# Web_Radio_Control_morse_key_USB_adapter.net
KiCad netlist of a schematic drawn in EasyEDA
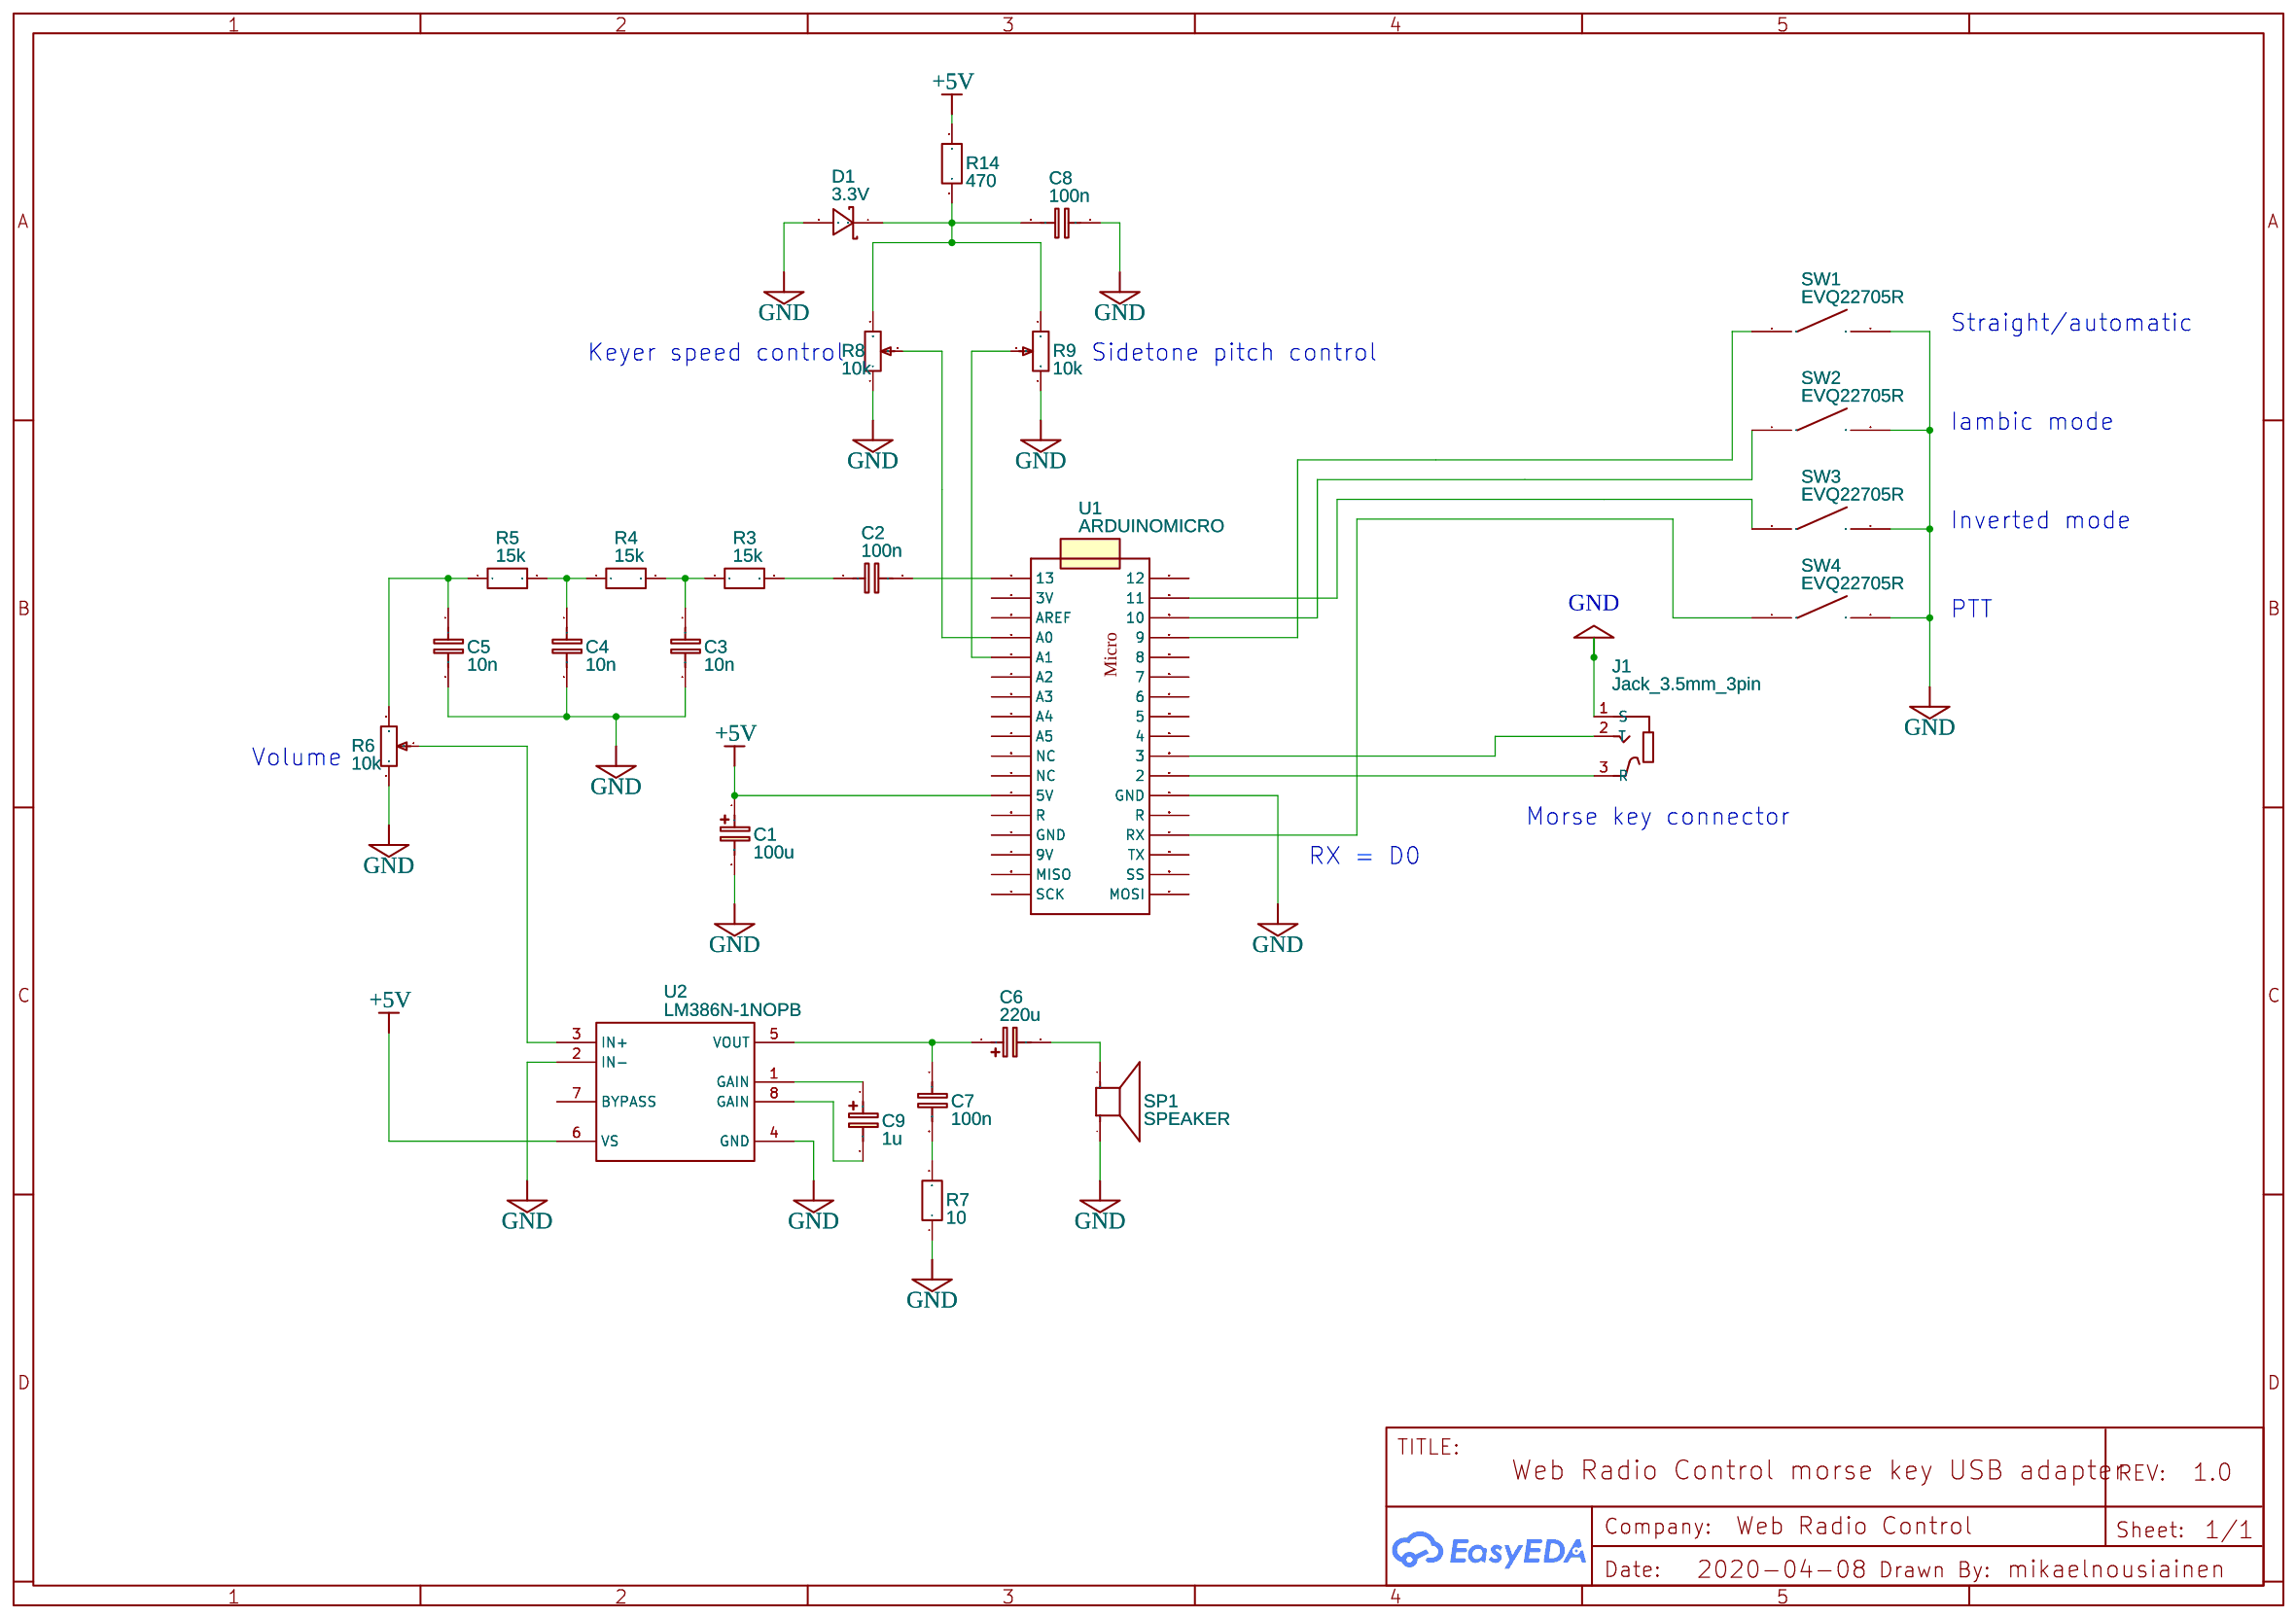
[diagram p0: schematic sheet]

(export (version "E")
  (design (tool "Eeschema 10.0.6"))
  (components
    (comp (ref "C1") (value "100u") (libsource (lib "") (part "Cap_Electrolytic(TH)_D3.0XF1.5_EU")))
    (comp (ref "C2") (value "100n") (libsource (lib "") (part "Cap_RAD-0.1_EU")))
    (comp (ref "C3") (value "10n") (libsource (lib "") (part "Cap_RAD-0.1_EU_2")))
    (comp (ref "C4") (value "10n") (libsource (lib "") (part "Cap_RAD-0.1_EU_2")))
    (comp (ref "C5") (value "10n") (libsource (lib "") (part "Cap_RAD-0.1_EU_2")))
    (comp (ref "C6") (value "220u") (libsource (lib "") (part "Cap_Electrolytic(TH)_D3.0XF1.5_EU_1")))
    (comp (ref "C7") (value "100n") (libsource (lib "") (part "Cap_RAD-0.1_EU_2")))
    (comp (ref "C8") (value "100n") (libsource (lib "") (part "Cap_RAD-0.1_EU_1")))
    (comp (ref "C9") (value "1u") (libsource (lib "") (part "Cap_Electrolytic(TH)_D3.0XF1.5_EU_2")))
    (comp (ref "D1")
      (value "3.3V")
      (fields
        (field (name "BOM_Manufacturer Part") "MBR0520LT1G")
        (field (name "BOM_Supplier Part") "C23848")
      )
      (libsource (lib "") (part "MBR0520LT1G"))
    )
    (comp (ref "J1") (value "Jack_3.5mm_3pin") (libsource (lib "") (part "Jack_3.5mm_3pin")))
    (comp (ref "R3") (value "15k") (libsource (lib "") (part "Res_AXIAL-0.3(1/8W)_EU_2")))
    (comp (ref "R4") (value "15k") (libsource (lib "") (part "Res_AXIAL-0.3(1/8W)_EU_2")))
    (comp (ref "R5") (value "15k") (libsource (lib "") (part "Res_AXIAL-0.3(1/8W)_EU_2")))
    (comp (ref "R6")
      (value "10k")
      (fields
        (field (name "BOM_Manufacturer Part") "3386P-1-101LF")
        (field (name "BOM_Supplier Part") "C125022")
      )
      (libsource (lib "") (part "3386P-1-101LF"))
    )
    (comp (ref "R7") (value "10") (libsource (lib "") (part "Res_AXIAL-0.3(1/8W)_EU")))
    (comp (ref "R8")
      (value "10k")
      (fields
        (field (name "BOM_Manufacturer Part") "3386P-1-101LF")
        (field (name "BOM_Supplier Part") "C125022")
      )
      (libsource (lib "") (part "3386P-1-101LF"))
    )
    (comp (ref "R9")
      (value "10k")
      (fields
        (field (name "BOM_Manufacturer Part") "3386P-1-101LF")
        (field (name "BOM_Supplier Part") "C125022")
      )
      (libsource (lib "") (part "3386P-1-101LF_1"))
    )
    (comp (ref "R14") (value "470") (libsource (lib "") (part "Res_AXIAL-0.3(1/8W)_EU_1")))
    (comp (ref "SP1") (value "SPEAKER") (libsource (lib "") (part "SPEAKER")))
    (comp (ref "SW1")
      (value "EVQ22705R")
      (fields (field (name "BOM_Supplier Part") "C79156"))
      (libsource (lib "") (part "EVQ22705R"))
    )
    (comp (ref "SW2")
      (value "EVQ22705R")
      (fields (field (name "BOM_Supplier Part") "C79156"))
      (libsource (lib "") (part "EVQ22705R"))
    )
    (comp (ref "SW3")
      (value "EVQ22705R")
      (fields (field (name "BOM_Supplier Part") "C79156"))
      (libsource (lib "") (part "EVQ22705R"))
    )
    (comp (ref "SW4")
      (value "EVQ22705R")
      (fields (field (name "BOM_Supplier Part") "C79156"))
      (libsource (lib "") (part "EVQ22705R"))
    )
    (comp (ref "U1") (value "ARDUINOMICRO") (libsource (lib "") (part "ARDUINOMICRO")))
    (comp (ref "U2") (value "LM386N-1NOPB") (libsource (lib "") (part "LM386N-1NOPB")))
  )
  (nets
    (net (code "1") (name "+5V") (class "Default")
      (node (ref "C1") (pin "1") (pinfunction "1_1") (pintype "unspecified"))
      (node (ref "R14") (pin "1") (pinfunction "1_1") (pintype "unspecified"))
      (node (ref "U1") (pin "P$23") (pinfunction "5V_P$23") (pintype "unspecified"))
      (node (ref "U2") (pin "6") (pinfunction "VS_6") (pintype "passive"))
    )
    (net (code "2") (name "GND") (class "Default")
      (node (ref "C1") (pin "2") (pinfunction "2_2") (pintype "unspecified"))
      (node (ref "C3") (pin "2") (pinfunction "2_2") (pintype "unspecified"))
      (node (ref "C4") (pin "2") (pinfunction "2_2") (pintype "unspecified"))
      (node (ref "C5") (pin "2") (pinfunction "2_2") (pintype "unspecified"))
      (node (ref "C8") (pin "1") (pinfunction "1_1") (pintype "unspecified"))
      (node (ref "D1") (pin "2") (pinfunction "A_2") (pintype "unspecified"))
      (node (ref "J1") (pin "1") (pinfunction "S_1") (pintype "unspecified"))
      (node (ref "R6") (pin "1") (pinfunction "1_1") (pintype "input"))
      (node (ref "R7") (pin "1") (pinfunction "1_1") (pintype "unspecified"))
      (node (ref "R8") (pin "1") (pinfunction "1_1") (pintype "input"))
      (node (ref "R9") (pin "3") (pinfunction "3_3") (pintype "input"))
      (node (ref "SP1") (pin "-") (pinfunction "-_-") (pintype "unspecified"))
      (node (ref "SW1") (pin "2") (pinfunction "2_2") (pintype "input"))
      (node (ref "SW2") (pin "2") (pinfunction "2_2") (pintype "input"))
      (node (ref "SW3") (pin "2") (pinfunction "2_2") (pintype "input"))
      (node (ref "SW4") (pin "2") (pinfunction "2_2") (pintype "input"))
      (node (ref "U1") (pin "P$21") (pinfunction "GND_P$21") (pintype "unspecified"))
      (node (ref "U2") (pin "2") (pinfunction "IN-_2") (pintype "unspecified"))
      (node (ref "U2") (pin "4") (pinfunction "GND_4") (pintype "passive"))
    )
    (net (code "3") (name "Net-(C2-Pad1)") (class "Default")
      (node (ref "C2") (pin "1") (pinfunction "1_1") (pintype "unspecified"))
      (node (ref "R3") (pin "2") (pinfunction "2_2") (pintype "unspecified"))
    )
    (net (code "4") (name "Net-(C3-Pad1)") (class "Default")
      (node (ref "C3") (pin "1") (pinfunction "1_1") (pintype "unspecified"))
      (node (ref "R3") (pin "1") (pinfunction "1_1") (pintype "unspecified"))
      (node (ref "R4") (pin "2") (pinfunction "2_2") (pintype "unspecified"))
    )
    (net (code "5") (name "Net-(C4-Pad1)") (class "Default")
      (node (ref "C4") (pin "1") (pinfunction "1_1") (pintype "unspecified"))
      (node (ref "R4") (pin "1") (pinfunction "1_1") (pintype "unspecified"))
      (node (ref "R5") (pin "2") (pinfunction "2_2") (pintype "unspecified"))
    )
    (net (code "6") (name "Net-(C5-Pad1)") (class "Default")
      (node (ref "C5") (pin "1") (pinfunction "1_1") (pintype "unspecified"))
      (node (ref "R5") (pin "1") (pinfunction "1_1") (pintype "unspecified"))
      (node (ref "R6") (pin "3") (pinfunction "3_3") (pintype "input"))
    )
    (net (code "7") (name "Net-(C6-Pad2)") (class "Default")
      (node (ref "C6") (pin "2") (pinfunction "2_2") (pintype "unspecified"))
      (node (ref "SP1") (pin "+") (pinfunction "+_+") (pintype "unspecified"))
    )
    (net (code "8") (name "Net-(C7-Pad2)") (class "Default")
      (node (ref "C7") (pin "2") (pinfunction "2_2") (pintype "unspecified"))
      (node (ref "R7") (pin "2") (pinfunction "2_2") (pintype "unspecified"))
    )
    (net (code "9") (name "Net-(C9-Pad1)") (class "Default")
      (node (ref "C9") (pin "1") (pinfunction "1_1") (pintype "unspecified"))
      (node (ref "U2") (pin "1") (pinfunction "GAIN_1") (pintype "unspecified"))
    )
    (net (code "10") (name "Net-(C9-Pad2)") (class "Default")
      (node (ref "C9") (pin "2") (pinfunction "2_2") (pintype "unspecified"))
      (node (ref "U2") (pin "8") (pinfunction "GAIN_8") (pintype "unspecified"))
    )
    (net (code "11") (name "Net-(D1-C)") (class "Default")
      (node (ref "C8") (pin "2") (pinfunction "2_2") (pintype "unspecified"))
      (node (ref "D1") (pin "1") (pinfunction "C_1") (pintype "unspecified"))
      (node (ref "R14") (pin "2") (pinfunction "2_2") (pintype "unspecified"))
      (node (ref "R8") (pin "3") (pinfunction "3_3") (pintype "input"))
      (node (ref "R9") (pin "1") (pinfunction "1_1") (pintype "input"))
    )
    (net (code "12") (name "Net-(J1-R)") (class "Default")
      (node (ref "J1") (pin "3") (pinfunction "R_3") (pintype "unspecified"))
      (node (ref "U1") (pin "P$11") (pinfunction "2_P$11") (pintype "unspecified"))
    )
    (net (code "13") (name "Net-(J1-T)") (class "Default")
      (node (ref "J1") (pin "2") (pinfunction "T_2") (pintype "unspecified"))
      (node (ref "U1") (pin "P$10") (pinfunction "3_P$10") (pintype "unspecified"))
    )
    (net (code "14") (name "Net-(U1-9)") (class "Default")
      (node (ref "SW1") (pin "1") (pinfunction "1_1") (pintype "input"))
      (node (ref "U1") (pin "P$4") (pinfunction "9_P$4") (pintype "unspecified"))
    )
    (net (code "15") (name "Net-(U1-10)") (class "Default")
      (node (ref "SW2") (pin "1") (pinfunction "1_1") (pintype "input"))
      (node (ref "U1") (pin "P$3") (pinfunction "10_P$3") (pintype "unspecified"))
    )
    (net (code "16") (name "Net-(U1-11)") (class "Default")
      (node (ref "SW3") (pin "1") (pinfunction "1_1") (pintype "input"))
      (node (ref "U1") (pin "P$2") (pinfunction "11_P$2") (pintype "unspecified"))
    )
    (net (code "17") (name "Net-(U1-13)") (class "Default")
      (node (ref "C2") (pin "2") (pinfunction "2_2") (pintype "unspecified"))
      (node (ref "U1") (pin "P$34") (pinfunction "13_P$34") (pintype "unspecified"))
    )
    (net (code "18") (name "Net-(U1-A0)") (class "Default")
      (node (ref "R8") (pin "2") (pinfunction "2_2") (pintype "input"))
      (node (ref "U1") (pin "P$31") (pinfunction "A0_P$31") (pintype "unspecified"))
    )
    (net (code "19") (name "Net-(U1-A1)") (class "Default")
      (node (ref "R9") (pin "2") (pinfunction "2_2") (pintype "input"))
      (node (ref "U1") (pin "P$30") (pinfunction "A1_P$30") (pintype "unspecified"))
    )
    (net (code "20") (name "Net-(U1-RX)") (class "Default")
      (node (ref "SW4") (pin "1") (pinfunction "1_1") (pintype "input"))
      (node (ref "U1") (pin "P$14") (pinfunction "RX_P$14") (pintype "unspecified"))
    )
    (net (code "21") (name "Net-(U2-IN+)") (class "Default")
      (node (ref "R6") (pin "2") (pinfunction "2_2") (pintype "input"))
      (node (ref "U2") (pin "3") (pinfunction "IN+_3") (pintype "unspecified"))
    )
    (net (code "22") (name "Net-(U2-VOUT)") (class "Default")
      (node (ref "C6") (pin "1") (pinfunction "1_1") (pintype "unspecified"))
      (node (ref "C7") (pin "1") (pinfunction "1_1") (pintype "unspecified"))
      (node (ref "U2") (pin "5") (pinfunction "VOUT_5") (pintype "output"))
    )
    (net (code "23") (name "unconnected-(U1-3V-PadP$33)") (class "Default")
      (node (ref "U1") (pin "P$33") (pinfunction "3V_P$33") (pintype "unspecified"))
    )
    (net (code "24") (name "unconnected-(U1-4-PadP$9)") (class "Default")
      (node (ref "U1") (pin "P$9") (pinfunction "4_P$9") (pintype "unspecified"))
    )
    (net (code "25") (name "unconnected-(U1-5-PadP$8)") (class "Default")
      (node (ref "U1") (pin "P$8") (pinfunction "5_P$8") (pintype "unspecified"))
    )
    (net (code "26") (name "unconnected-(U1-6-PadP$7)") (class "Default")
      (node (ref "U1") (pin "P$7") (pinfunction "6_P$7") (pintype "unspecified"))
    )
    (net (code "27") (name "unconnected-(U1-7-PadP$6)") (class "Default")
      (node (ref "U1") (pin "P$6") (pinfunction "7_P$6") (pintype "unspecified"))
    )
    (net (code "28") (name "unconnected-(U1-8-PadP$5)") (class "Default")
      (node (ref "U1") (pin "P$5") (pinfunction "8_P$5") (pintype "unspecified"))
    )
    (net (code "29") (name "unconnected-(U1-9V-PadP$20)") (class "Default")
      (node (ref "U1") (pin "P$20") (pinfunction "9V_P$20") (pintype "unspecified"))
    )
    (net (code "30") (name "unconnected-(U1-12-PadP$1)") (class "Default")
      (node (ref "U1") (pin "P$1") (pinfunction "12_P$1") (pintype "unspecified"))
    )
    (net (code "31") (name "unconnected-(U1-A2-PadP$29)") (class "Default")
      (node (ref "U1") (pin "P$29") (pinfunction "A2_P$29") (pintype "unspecified"))
    )
    (net (code "32") (name "unconnected-(U1-A3-PadP$28)") (class "Default")
      (node (ref "U1") (pin "P$28") (pinfunction "A3_P$28") (pintype "unspecified"))
    )
    (net (code "33") (name "unconnected-(U1-A4-PadP$27)") (class "Default")
      (node (ref "U1") (pin "P$27") (pinfunction "A4_P$27") (pintype "unspecified"))
    )
    (net (code "34") (name "unconnected-(U1-A5-PadP$26)") (class "Default")
      (node (ref "U1") (pin "P$26") (pinfunction "A5_P$26") (pintype "unspecified"))
    )
    (net (code "35") (name "unconnected-(U1-AREF-PadP$32)") (class "Default")
      (node (ref "U1") (pin "P$32") (pinfunction "AREF_P$32") (pintype "unspecified"))
    )
    (net (code "36") (name "unconnected-(U1-GND-PadP$12)") (class "Default")
      (node (ref "U1") (pin "P$12") (pinfunction "GND_P$12") (pintype "unspecified"))
    )
    (net (code "37") (name "unconnected-(U1-MISO-PadP$19)") (class "Default")
      (node (ref "U1") (pin "P$19") (pinfunction "MISO_P$19") (pintype "unspecified"))
    )
    (net (code "38") (name "unconnected-(U1-MOSI-PadP$17)") (class "Default")
      (node (ref "U1") (pin "P$17") (pinfunction "MOSI_P$17") (pintype "unspecified"))
    )
    (net (code "39") (name "unconnected-(U1-NC-PadP$24)") (class "Default")
      (node (ref "U1") (pin "P$24") (pinfunction "NC_P$24") (pintype "unspecified"))
    )
    (net (code "40") (name "unconnected-(U1-NC-PadP$25)") (class "Default")
      (node (ref "U1") (pin "P$25") (pinfunction "NC_P$25") (pintype "unspecified"))
    )
    (net (code "41") (name "unconnected-(U1-R-PadP$13)") (class "Default")
      (node (ref "U1") (pin "P$13") (pinfunction "R_P$13") (pintype "unspecified"))
    )
    (net (code "42") (name "unconnected-(U1-R-PadP$22)") (class "Default")
      (node (ref "U1") (pin "P$22") (pinfunction "R_P$22") (pintype "unspecified"))
    )
    (net (code "43") (name "unconnected-(U1-SCK-PadP$18)") (class "Default")
      (node (ref "U1") (pin "P$18") (pinfunction "SCK_P$18") (pintype "unspecified"))
    )
    (net (code "44") (name "unconnected-(U1-SS-PadP$16)") (class "Default")
      (node (ref "U1") (pin "P$16") (pinfunction "SS_P$16") (pintype "unspecified"))
    )
    (net (code "45") (name "unconnected-(U1-TX-PadP$15)") (class "Default")
      (node (ref "U1") (pin "P$15") (pinfunction "TX_P$15") (pintype "unspecified"))
    )
    (net (code "46") (name "unconnected-(U2-BYPASS-Pad7)") (class "Default")
      (node (ref "U2") (pin "7") (pinfunction "BYPASS_7") (pintype "unspecified"))
    )
  )
)
